# simreader_marble_hammi_CH340.net
KiCad netlist of a schematic drawn in EAGLE
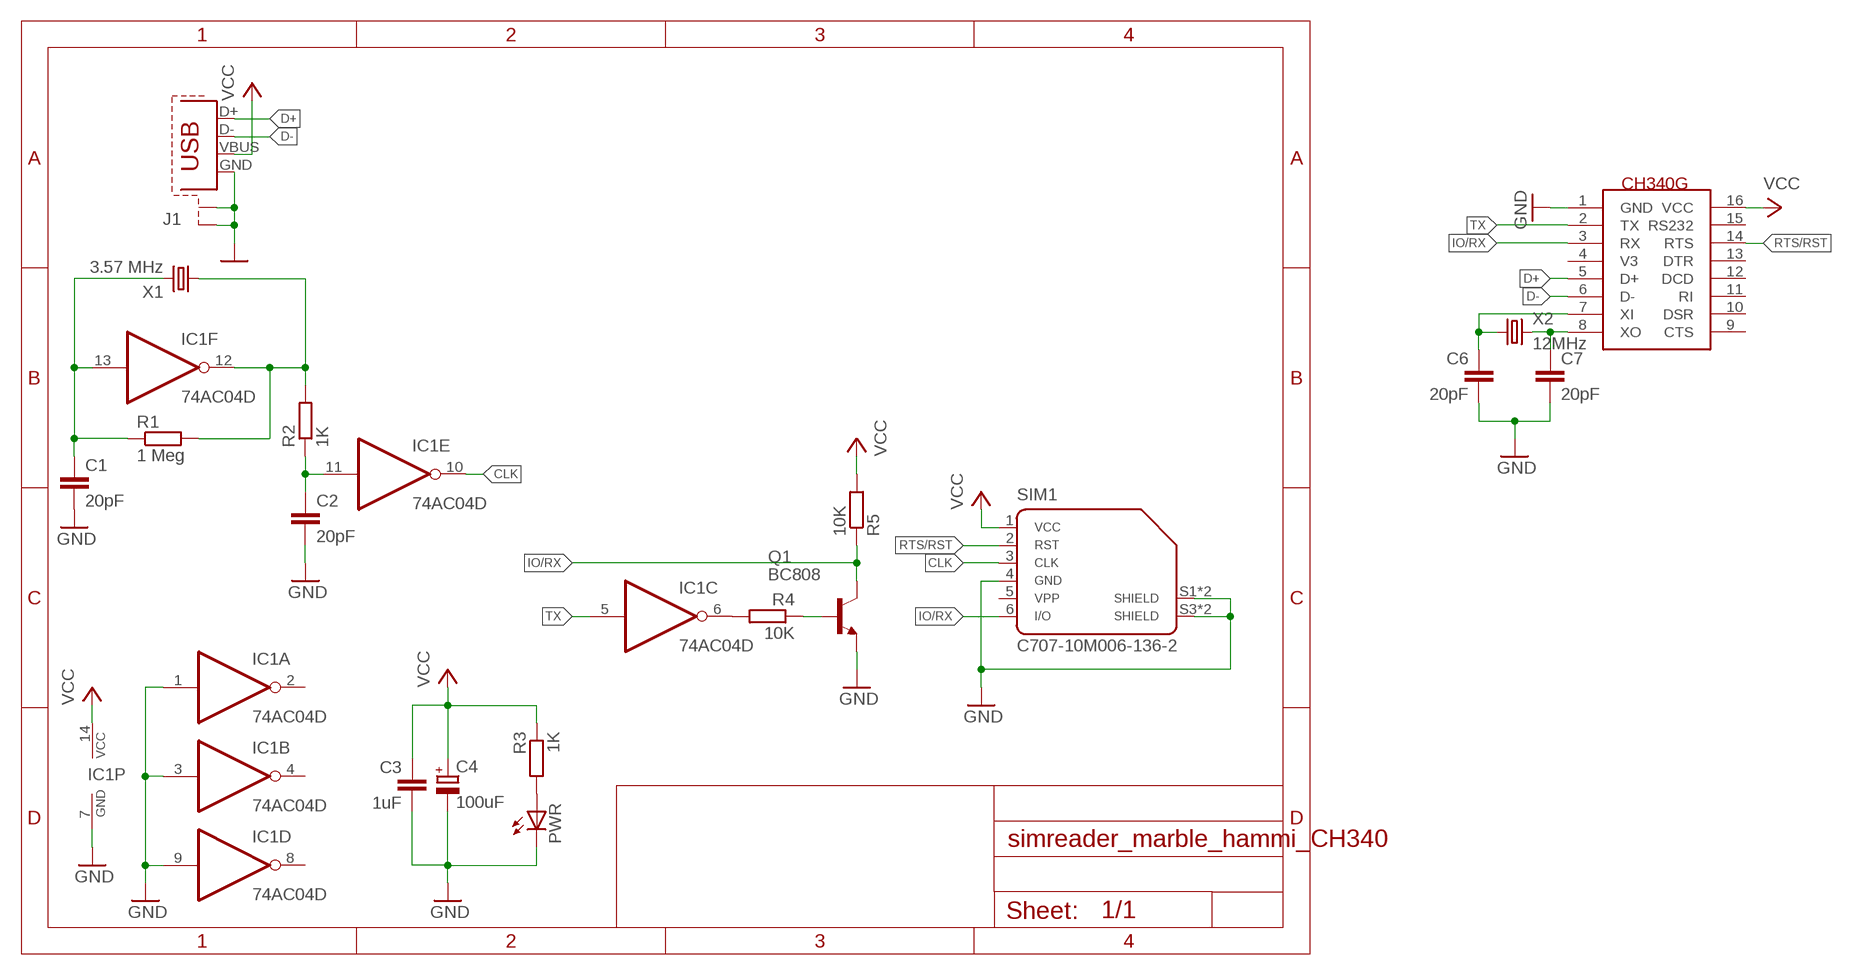
[diagram p0: schematic, sheet 1]

(export (version "E")
  (design (tool "Eeschema 10.0.6"))
  (components
    (comp (ref "C1")
      (value "20pF")
      (footprint "eagle-import:C0603")
      (libsource (lib "eagle-import") (part "C-EUC0603"))
    )
    (comp (ref "C2")
      (value "20pF")
      (footprint "eagle-import:C0603")
      (libsource (lib "eagle-import") (part "C-EUC0603"))
    )
    (comp (ref "C3")
      (value "1uF")
      (footprint "eagle-import:C0603")
      (libsource (lib "eagle-import") (part "C-EUC0603"))
    )
    (comp (ref "C4")
      (value "100uF")
      (footprint "eagle-import:140CLH-0810")
      (libsource (lib "eagle-import") (part "CPOL-EU140CLH-0810"))
    )
    (comp (ref "C6")
      (value "20pF")
      (footprint "eagle-import:C0603")
      (libsource (lib "eagle-import") (part "C-EUC0603"))
    )
    (comp (ref "C7")
      (value "20pF")
      (footprint "eagle-import:C0603")
      (libsource (lib "eagle-import") (part "C-EUC0603"))
    )
    (comp (ref "IC1")
      (value "74AC04D")
      (footprint "eagle-import:SO14")
      (libsource (lib "eagle-import") (part "7404DAC"))
    )
    (comp (ref "IC2")
      (value "CH340G")
      (footprint "eagle-import:CH340G")
      (libsource (lib "eagle-import") (part "CH340G"))
    )
    (comp (ref "J1")
      (value "USB-SHIELD-A-H")
      (footprint "eagle-import:USB-A-H")
      (libsource (lib "eagle-import") (part "USB-SHIELD-A-H"))
    )
    (comp (ref "PWR")
      (value "LEDCHIPLED_0603")
      (footprint "eagle-import:CHIPLED_0603")
      (libsource (lib "eagle-import") (part "LEDCHIPLED_0603"))
    )
    (comp (ref "Q1")
      (value "BC808")
      (footprint "eagle-import:SOT23-BEC")
      (libsource (lib "eagle-import") (part "-NPN-SOT23-BECBC808"))
    )
    (comp (ref "R1")
      (value "1 Meg")
      (footprint "eagle-import:R0603")
      (libsource (lib "eagle-import") (part "R-EU_R0603"))
    )
    (comp (ref "R2")
      (value "1K")
      (footprint "eagle-import:R0603")
      (libsource (lib "eagle-import") (part "R-EU_R0603"))
    )
    (comp (ref "R3")
      (value "1K")
      (footprint "eagle-import:R0603")
      (libsource (lib "eagle-import") (part "R-EU_R0603"))
    )
    (comp (ref "R4")
      (value "10K")
      (footprint "eagle-import:R0603")
      (libsource (lib "eagle-import") (part "R-EU_R0603"))
    )
    (comp (ref "R5")
      (value "10K")
      (footprint "eagle-import:R0603")
      (libsource (lib "eagle-import") (part "R-EU_R0603"))
    )
    (comp (ref "SIM1")
      (value "C707-10M006-136-2")
      (footprint "eagle-import:C707_10M006_136_2")
      (libsource (lib "eagle-import") (part "C707-10M006-136-2"))
    )
    (comp (ref "X1")
      (value "3.57 MHz")
      (footprint "eagle-import:HC49UP")
      (libsource (lib "eagle-import") (part "CRYSTALHC49UP"))
    )
    (comp (ref "X2")
      (value "12MHz")
      (footprint "eagle-import:HC49UP")
      (libsource (lib "eagle-import") (part "CRYSTALHC49UP"))
    )
  )
  (nets
    (net (code "1") (name "CLK") (class "Default")
      (node (ref "IC1") (pin "10") (pinfunction "O_10") (pintype "output"))
      (node (ref "SIM1") (pin "3") (pinfunction "3_3") (pintype "passive"))
    )
    (net (code "2") (name "D+") (class "Default")
      (node (ref "IC2") (pin "5") (pinfunction "D+_5") (pintype "bidirectional"))
      (node (ref "J1") (pin "D+") (pinfunction "D+_D+") (pintype "passive"))
    )
    (net (code "3") (name "D-") (class "Default")
      (node (ref "IC2") (pin "6") (pinfunction "D-_6") (pintype "bidirectional"))
      (node (ref "J1") (pin "D-") (pinfunction "D-_D-") (pintype "passive"))
    )
    (net (code "4") (name "GND") (class "Default")
      (node (ref "C1") (pin "2") (pinfunction "2_2") (pintype "passive"))
      (node (ref "C2") (pin "2") (pinfunction "2_2") (pintype "passive"))
      (node (ref "C3") (pin "2") (pinfunction "2_2") (pintype "passive"))
      (node (ref "C4") (pin "-") (pinfunction "-_-") (pintype "passive"))
      (node (ref "C6") (pin "2") (pinfunction "2_2") (pintype "passive"))
      (node (ref "C7") (pin "2") (pinfunction "2_2") (pintype "passive"))
      (node (ref "IC1") (pin "1") (pinfunction "I_1") (pintype "input"))
      (node (ref "IC1") (pin "3") (pinfunction "I_3") (pintype "input"))
      (node (ref "IC1") (pin "7") (pinfunction "GND_7") (pintype "power_in"))
      (node (ref "IC1") (pin "9") (pinfunction "I_9") (pintype "input"))
      (node (ref "IC2") (pin "1") (pinfunction "GND_1") (pintype "bidirectional"))
      (node (ref "J1") (pin "GND") (pinfunction "GND_GND") (pintype "passive"))
      (node (ref "J1") (pin "GND2") (pinfunction "S1_GND2") (pintype "passive"))
      (node (ref "J1") (pin "GND3") (pinfunction "S2_GND3") (pintype "passive"))
      (node (ref "PWR") (pin "C") (pinfunction "C_C") (pintype "passive"))
      (node (ref "Q1") (pin "E") (pinfunction "E_E") (pintype "passive"))
      (node (ref "SIM1") (pin "4") (pinfunction "4_4") (pintype "passive"))
      (node (ref "SIM1") (pin "S1") (pinfunction "S1_S1") (pintype "passive"))
      (node (ref "SIM1") (pin "S2") (pinfunction "S1_S2") (pintype "passive"))
      (node (ref "SIM1") (pin "S3") (pinfunction "S2_S3") (pintype "passive"))
      (node (ref "SIM1") (pin "S4") (pinfunction "S2_S4") (pintype "passive"))
    )
    (net (code "5") (name "IO{slash}RX") (class "Default")
      (node (ref "IC2") (pin "3") (pinfunction "RX_3") (pintype "bidirectional"))
      (node (ref "Q1") (pin "C") (pinfunction "C_C") (pintype "passive"))
      (node (ref "R5") (pin "1") (pinfunction "1_1") (pintype "passive"))
      (node (ref "SIM1") (pin "6") (pinfunction "6_6") (pintype "passive"))
    )
    (net (code "6") (name "Net-(IC1C-O)") (class "Default")
      (node (ref "IC1") (pin "6") (pinfunction "O_6") (pintype "output"))
      (node (ref "R4") (pin "2") (pinfunction "2_2") (pintype "passive"))
    )
    (net (code "7") (name "Net-(IC1E-I)") (class "Default")
      (node (ref "C2") (pin "1") (pinfunction "1_1") (pintype "passive"))
      (node (ref "IC1") (pin "11") (pinfunction "I_11") (pintype "input"))
      (node (ref "R2") (pin "1") (pinfunction "1_1") (pintype "passive"))
    )
    (net (code "8") (name "Net-(IC1F-I)") (class "Default")
      (node (ref "C1") (pin "1") (pinfunction "1_1") (pintype "passive"))
      (node (ref "IC1") (pin "13") (pinfunction "I_13") (pintype "input"))
      (node (ref "R1") (pin "1") (pinfunction "1_1") (pintype "passive"))
      (node (ref "X1") (pin "2") (pinfunction "2_2") (pintype "passive"))
    )
    (net (code "9") (name "Net-(IC1F-O)") (class "Default")
      (node (ref "IC1") (pin "12") (pinfunction "O_12") (pintype "output"))
      (node (ref "R1") (pin "2") (pinfunction "2_2") (pintype "passive"))
      (node (ref "R2") (pin "2") (pinfunction "2_2") (pintype "passive"))
      (node (ref "X1") (pin "1") (pinfunction "1_1") (pintype "passive"))
    )
    (net (code "10") (name "Net-(IC2-XI)") (class "Default")
      (node (ref "C6") (pin "1") (pinfunction "1_1") (pintype "passive"))
      (node (ref "IC2") (pin "7") (pinfunction "XI_7") (pintype "bidirectional"))
      (node (ref "X2") (pin "1") (pinfunction "1_1") (pintype "passive"))
    )
    (net (code "11") (name "Net-(IC2-XO)") (class "Default")
      (node (ref "C7") (pin "1") (pinfunction "1_1") (pintype "passive"))
      (node (ref "IC2") (pin "8") (pinfunction "XO_8") (pintype "bidirectional"))
      (node (ref "X2") (pin "2") (pinfunction "2_2") (pintype "passive"))
    )
    (net (code "12") (name "Net-(PWR-PadA)") (class "Default")
      (node (ref "PWR") (pin "A") (pinfunction "A_A") (pintype "passive"))
      (node (ref "R3") (pin "2") (pinfunction "2_2") (pintype "passive"))
    )
    (net (code "13") (name "Net-(Q1-PadB)") (class "Default")
      (node (ref "Q1") (pin "B") (pinfunction "B_B") (pintype "passive"))
      (node (ref "R4") (pin "1") (pinfunction "1_1") (pintype "passive"))
    )
    (net (code "14") (name "RTS{slash}RST") (class "Default")
      (node (ref "IC2") (pin "14") (pinfunction "RTS_14") (pintype "bidirectional"))
      (node (ref "SIM1") (pin "2") (pinfunction "2_2") (pintype "passive"))
    )
    (net (code "15") (name "TX") (class "Default")
      (node (ref "IC1") (pin "5") (pinfunction "I_5") (pintype "input"))
      (node (ref "IC2") (pin "2") (pinfunction "TX_2") (pintype "bidirectional"))
    )
    (net (code "16") (name "VCC") (class "Default")
      (node (ref "C3") (pin "1") (pinfunction "1_1") (pintype "passive"))
      (node (ref "C4") (pin "+") (pinfunction "+_+") (pintype "passive"))
      (node (ref "IC1") (pin "14") (pinfunction "VCC_14") (pintype "power_in"))
      (node (ref "IC2") (pin "16") (pinfunction "VCC_16") (pintype "bidirectional"))
      (node (ref "J1") (pin "VBUS") (pinfunction "VBUS_VBUS") (pintype "passive"))
      (node (ref "R3") (pin "1") (pinfunction "1_1") (pintype "passive"))
      (node (ref "R5") (pin "2") (pinfunction "2_2") (pintype "passive"))
      (node (ref "SIM1") (pin "1") (pinfunction "1_1") (pintype "passive"))
    )
    (net (code "17") (name "unconnected-(IC1A-O-Pad2)") (class "Default")
      (node (ref "IC1") (pin "2") (pinfunction "O_2") (pintype "output"))
    )
    (net (code "18") (name "unconnected-(IC1B-O-Pad4)") (class "Default")
      (node (ref "IC1") (pin "4") (pinfunction "O_4") (pintype "output"))
    )
    (net (code "19") (name "unconnected-(IC1D-O-Pad8)") (class "Default")
      (node (ref "IC1") (pin "8") (pinfunction "O_8") (pintype "output"))
    )
    (net (code "20") (name "unconnected-(IC2-CTS-Pad9)") (class "Default")
      (node (ref "IC2") (pin "9") (pinfunction "CTS_9") (pintype "bidirectional"))
    )
    (net (code "21") (name "unconnected-(IC2-DCD-Pad12)") (class "Default")
      (node (ref "IC2") (pin "12") (pinfunction "DCD_12") (pintype "bidirectional"))
    )
    (net (code "22") (name "unconnected-(IC2-DSR-Pad10)") (class "Default")
      (node (ref "IC2") (pin "10") (pinfunction "DSR_10") (pintype "bidirectional"))
    )
    (net (code "23") (name "unconnected-(IC2-DTR-Pad13)") (class "Default")
      (node (ref "IC2") (pin "13") (pinfunction "DTR_13") (pintype "bidirectional"))
    )
    (net (code "24") (name "unconnected-(IC2-RI-Pad11)") (class "Default")
      (node (ref "IC2") (pin "11") (pinfunction "RI_11") (pintype "bidirectional"))
    )
    (net (code "25") (name "unconnected-(IC2-RS232-Pad15)") (class "Default")
      (node (ref "IC2") (pin "15") (pinfunction "RS232_15") (pintype "bidirectional"))
    )
    (net (code "26") (name "unconnected-(IC2-V3-Pad4)") (class "Default")
      (node (ref "IC2") (pin "4") (pinfunction "V3_4") (pintype "bidirectional"))
    )
    (net (code "27") (name "unconnected-(SIM1-Pad5)") (class "Default")
      (node (ref "SIM1") (pin "5") (pinfunction "5_5") (pintype "passive"))
    )
  )
)
